# PR5004.net
KiCad netlist of a schematic drawn in EAGLE
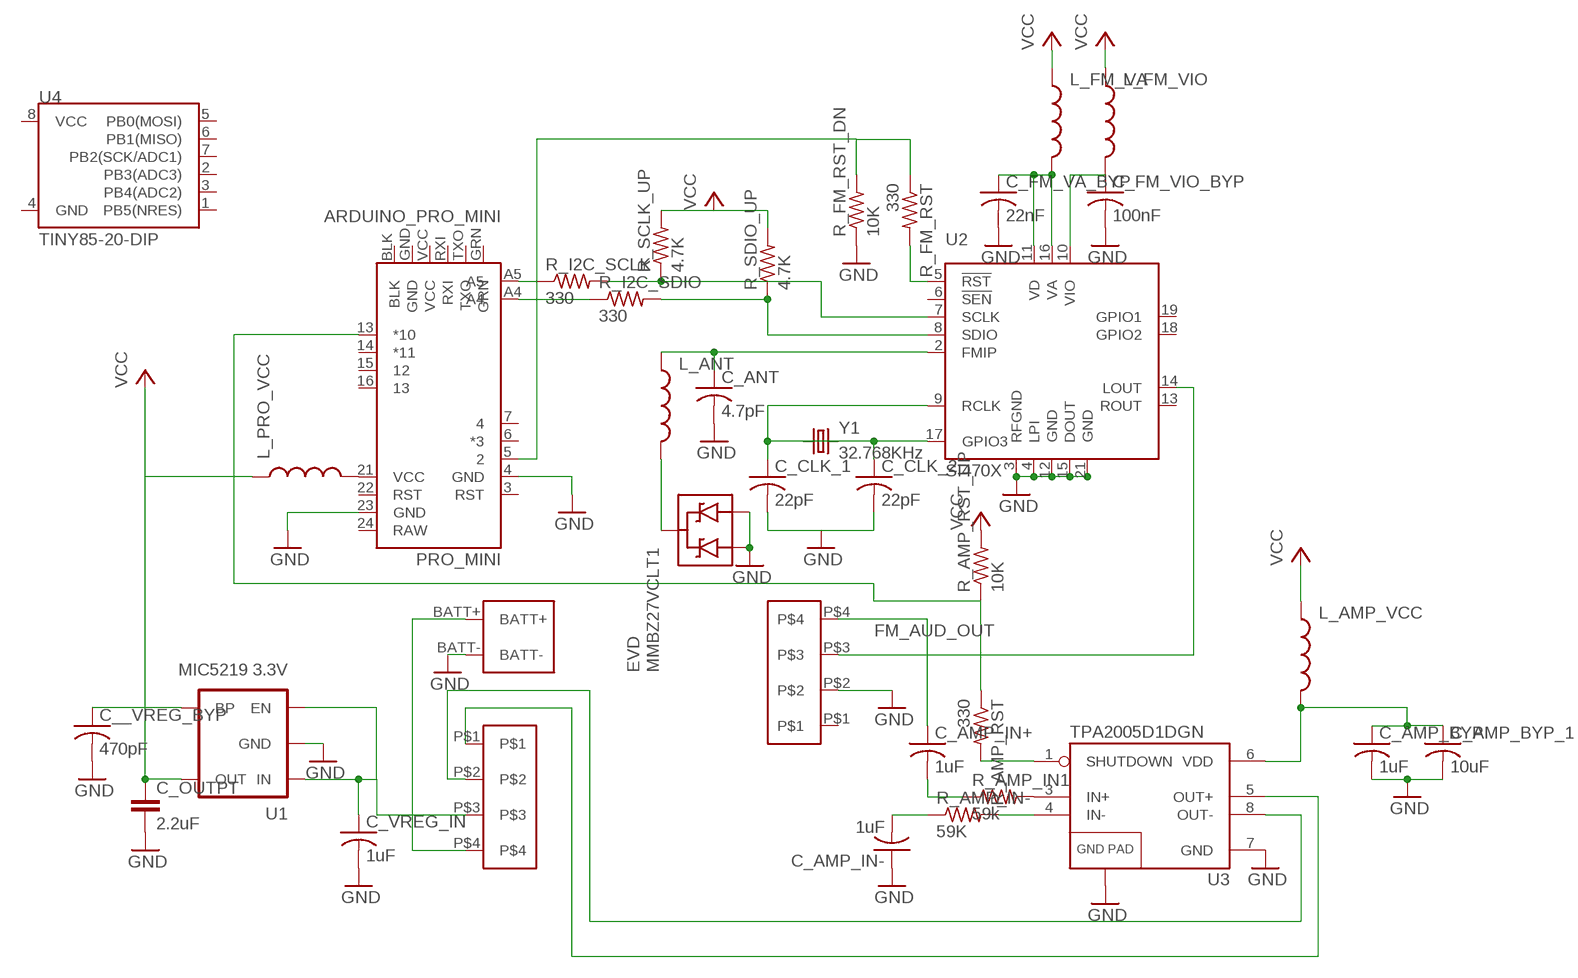
[diagram p0: schematic, sheet 1]

(export (version "E")
  (design (tool "Eeschema 10.0.6"))
  (components
    (comp (ref "ANT/POT_VOL")
      (value "OSTVN04")
      (footprint "eagle-import:OSTVN04")
      (libsource (lib "eagle-import") (part "OSTVN04"))
    )
    (comp (ref "ANT/POT_VOL1")
      (value "OSTVN04")
      (footprint "eagle-import:OSTVN04")
      (libsource (lib "eagle-import") (part "OSTVN04"))
    )
    (comp (ref "BATT_IN")
      (value "KEYSTONE_2479_3XAAA_BOTTOM")
      (footprint "eagle-import:KEYSTONE_2479_3XAAA_BOTTOM")
      (libsource (lib "eagle-import") (part "KEYSTONE_2479_3XAAA_BOTTOM"))
    )
    (comp (ref "C_AMP_BYP")
      (value "1uF")
      (footprint "eagle-import:C0603")
      (libsource (lib "eagle-import") (part "C-USC0603"))
    )
    (comp (ref "C_AMP_BYP_1")
      (value "10uF")
      (footprint "eagle-import:C0603")
      (libsource (lib "eagle-import") (part "C-USC0603"))
    )
    (comp (ref "C_AMP_IN+")
      (value "1uF")
      (footprint "eagle-import:C0603")
      (libsource (lib "eagle-import") (part "C-USC0603"))
    )
    (comp (ref "C_AMP_IN-")
      (value "1uF")
      (footprint "eagle-import:C0603")
      (libsource (lib "eagle-import") (part "C-USC0603"))
    )
    (comp (ref "C_ANT")
      (value "4.7pF")
      (footprint "eagle-import:C0805")
      (libsource (lib "eagle-import") (part "C-USC0805"))
    )
    (comp (ref "C_CLK_1")
      (value "22pF")
      (footprint "eagle-import:C0603")
      (libsource (lib "eagle-import") (part "C-USC0603"))
    )
    (comp (ref "C_CLK_2")
      (value "22pF")
      (footprint "eagle-import:C0603")
      (libsource (lib "eagle-import") (part "C-USC0603"))
    )
    (comp (ref "C_FM_VA_BYP")
      (value "22nF")
      (footprint "eagle-import:C0603")
      (libsource (lib "eagle-import") (part "C-USC0603"))
    )
    (comp (ref "C_FM_VIO_BYP")
      (value "100nF")
      (footprint "eagle-import:C0603")
      (libsource (lib "eagle-import") (part "C-USC0603"))
    )
    (comp (ref "C_OUTPT")
      (value "2.2uF")
      (footprint "eagle-import:VISHAY_TR3C")
      (libsource (lib "eagle-import") (part "VISHAY_TR3C"))
    )
    (comp (ref "C_VREG_IN")
      (value "1uF")
      (footprint "eagle-import:C0603")
      (libsource (lib "eagle-import") (part "C-USC0603"))
    )
    (comp (ref "C__VREG_BYP")
      (value "470pF")
      (footprint "eagle-import:C0603")
      (libsource (lib "eagle-import") (part "C-USC0603"))
    )
    (comp (ref "EVD")
      (value "MMBZ27VCLT1")
      (footprint "eagle-import:SOT23-3")
      (libsource (lib "eagle-import") (part "MMBZ27VCLT1"))
    )
    (comp (ref "L_AMP_VCC")
      (value "INDUCTOR0603")
      (footprint "eagle-import:0603")
      (libsource (lib "eagle-import") (part "INDUCTOR0603"))
    )
    (comp (ref "L_ANT")
      (value "INDUCTOR0805")
      (footprint "eagle-import:0805")
      (libsource (lib "eagle-import") (part "INDUCTOR0805"))
    )
    (comp (ref "L_FM_VA")
      (value "INDUCTOR0603")
      (footprint "eagle-import:0603")
      (libsource (lib "eagle-import") (part "INDUCTOR0603"))
    )
    (comp (ref "L_FM_VIO")
      (value "INDUCTOR0603")
      (footprint "eagle-import:0603")
      (libsource (lib "eagle-import") (part "INDUCTOR0603"))
    )
    (comp (ref "L_PRO_VCC")
      (value "INDUCTOR0603")
      (footprint "eagle-import:0603")
      (libsource (lib "eagle-import") (part "INDUCTOR0603"))
    )
    (comp (ref "PRO_MINI")
      (value "ARDUINO_PRO_MINI")
      (footprint "eagle-import:ARDUINO_PRO_MINI")
      (libsource (lib "eagle-import") (part "ARDUINO_PRO_MINI"))
    )
    (comp (ref "R_AMP_IN-")
      (value "59K")
      (footprint "eagle-import:R0603")
      (libsource (lib "eagle-import") (part "R-US_R0603"))
    )
    (comp (ref "R_AMP_IN1")
      (value "59k")
      (footprint "eagle-import:R0603")
      (libsource (lib "eagle-import") (part "R-US_R0603"))
    )
    (comp (ref "R_AMP_RST")
      (value "330")
      (footprint "eagle-import:R0603")
      (libsource (lib "eagle-import") (part "R-US_R0603"))
    )
    (comp (ref "R_AMP_RST_UP")
      (value "10K")
      (footprint "eagle-import:R0603")
      (libsource (lib "eagle-import") (part "R-US_R0603"))
    )
    (comp (ref "R_FM_RST")
      (value "330")
      (footprint "eagle-import:R0603")
      (libsource (lib "eagle-import") (part "R-US_R0603"))
    )
    (comp (ref "R_FM_RST_DN")
      (value "10K")
      (footprint "eagle-import:R0603")
      (libsource (lib "eagle-import") (part "R-US_R0603"))
    )
    (comp (ref "R_I2C_SCLK")
      (value "330")
      (footprint "eagle-import:R0603")
      (libsource (lib "eagle-import") (part "R-US_R0603"))
    )
    (comp (ref "R_I2C_SDIO")
      (value "330")
      (footprint "eagle-import:R0603")
      (libsource (lib "eagle-import") (part "R-US_R0603"))
    )
    (comp (ref "R_SCLK_UP")
      (value "4.7K")
      (footprint "eagle-import:R0603")
      (libsource (lib "eagle-import") (part "R-US_R0603"))
    )
    (comp (ref "R_SDIO_UP")
      (value "4.7K")
      (footprint "eagle-import:R0603")
      (libsource (lib "eagle-import") (part "R-US_R0603"))
    )
    (comp (ref "U1")
      (value "MIC5219 3.3V")
      (footprint "eagle-import:SOT23-5")
      (libsource (lib "eagle-import") (part "V_REG_MIC52193.3V"))
    )
    (comp (ref "U2")
      (value "SI470X")
      (footprint "eagle-import:SI470X")
      (libsource (lib "eagle-import") (part "SI470X"))
    )
    (comp (ref "U3")
      (value "TPA2005D1DGN")
      (footprint "eagle-import:POWER-SOP8")
      (libsource (lib "eagle-import") (part "TPA2005D1DGN"))
    )
    (comp (ref "U4")
      (value "TINY85-20-DIP")
      (footprint "eagle-import:DIP08")
      (libsource (lib "eagle-import") (part "ATTINY45TINY85-20-DIP"))
    )
    (comp (ref "Y1")
      (value "32.768KHz")
      (footprint "eagle-import:CRYSTAL-32KHZ-SMD")
      (libsource (lib "eagle-import") (part "CRYSTAL32-SMD"))
    )
  )
  (nets
    (net (code "1") (name "/FM_AUD_OUT") (class "Default")
      (node (ref "ANT/POT_VOL") (pin "P$3") (pinfunction "P$3_P$3") (pintype "bidirectional"))
      (node (ref "U2") (pin "14") (pinfunction "LOUT_14") (pintype "bidirectional"))
    )
    (net (code "2") (name "GND") (class "Default")
      (node (ref "ANT/POT_VOL") (pin "P$2") (pinfunction "P$2_P$2") (pintype "bidirectional"))
      (node (ref "BATT_IN") (pin "BATT-") (pinfunction "BATT-_BATT-") (pintype "bidirectional"))
      (node (ref "C_AMP_BYP") (pin "2") (pinfunction "2_2") (pintype "passive"))
      (node (ref "C_AMP_BYP_1") (pin "2") (pinfunction "2_2") (pintype "passive"))
      (node (ref "C_AMP_IN-") (pin "1") (pinfunction "1_1") (pintype "passive"))
      (node (ref "C_ANT") (pin "2") (pinfunction "2_2") (pintype "passive"))
      (node (ref "C_CLK_1") (pin "2") (pinfunction "2_2") (pintype "passive"))
      (node (ref "C_CLK_2") (pin "2") (pinfunction "2_2") (pintype "passive"))
      (node (ref "C_FM_VA_BYP") (pin "2") (pinfunction "2_2") (pintype "passive"))
      (node (ref "C_FM_VIO_BYP") (pin "2") (pinfunction "2_2") (pintype "passive"))
      (node (ref "C_OUTPT") (pin "P$2") (pinfunction "2_P$2") (pintype "passive"))
      (node (ref "C_VREG_IN") (pin "2") (pinfunction "2_2") (pintype "passive"))
      (node (ref "C__VREG_BYP") (pin "2") (pinfunction "2_2") (pintype "passive"))
      (node (ref "EVD") (pin "1") (pinfunction "A1_1") (pintype "passive"))
      (node (ref "EVD") (pin "2") (pinfunction "A2_2") (pintype "passive"))
      (node (ref "PRO_MINI") (pin "23") (pinfunction "GND_23") (pintype "bidirectional"))
      (node (ref "PRO_MINI") (pin "4") (pinfunction "GND_4") (pintype "bidirectional"))
      (node (ref "R_FM_RST_DN") (pin "1") (pinfunction "1_1") (pintype "passive"))
      (node (ref "U1") (pin "2") (pinfunction "GND_2") (pintype "input"))
      (node (ref "U2") (pin "12") (pinfunction "GND_12") (pintype "bidirectional"))
      (node (ref "U2") (pin "15") (pinfunction "DOUT_15") (pintype "bidirectional"))
      (node (ref "U2") (pin "21") (pinfunction "GND_21") (pintype "bidirectional"))
      (node (ref "U2") (pin "3") (pinfunction "RFGND_3") (pintype "bidirectional"))
      (node (ref "U2") (pin "4") (pinfunction "LPI_4") (pintype "bidirectional"))
      (node (ref "U3") (pin "7") (pinfunction "GND_7") (pintype "power_in"))
      (node (ref "U3") (pin "9") (pinfunction "GND_9") (pintype "power_in"))
    )
    (net (code "3") (name "Net-(ANT/POT_VOL-PadP$4)") (class "Default")
      (node (ref "ANT/POT_VOL") (pin "P$4") (pinfunction "P$4_P$4") (pintype "bidirectional"))
      (node (ref "C_AMP_IN+") (pin "1") (pinfunction "1_1") (pintype "passive"))
    )
    (net (code "4") (name "Net-(ANT/POT_VOL1-PadP$4)") (class "Default")
      (node (ref "ANT/POT_VOL1") (pin "P$4") (pinfunction "P$4_P$4") (pintype "bidirectional"))
      (node (ref "BATT_IN") (pin "BATT+") (pinfunction "BATT+_BATT+") (pintype "bidirectional"))
    )
    (net (code "5") (name "Net-(C_AMP_IN+-Pad2)") (class "Default")
      (node (ref "C_AMP_IN+") (pin "2") (pinfunction "2_2") (pintype "passive"))
      (node (ref "R_AMP_IN1") (pin "1") (pinfunction "1_1") (pintype "passive"))
    )
    (net (code "6") (name "Net-(C_AMP_IN--Pad2)") (class "Default")
      (node (ref "C_AMP_IN-") (pin "2") (pinfunction "2_2") (pintype "passive"))
      (node (ref "R_AMP_IN-") (pin "1") (pinfunction "1_1") (pintype "passive"))
    )
    (net (code "7") (name "Net-(EVD-C)") (class "Default")
      (node (ref "EVD") (pin "3") (pinfunction "C_3") (pintype "passive"))
      (node (ref "L_ANT") (pin "2") (pinfunction "2_2") (pintype "passive"))
    )
    (net (code "8") (name "Net-(L_PRO_VCC-Pad2)") (class "Default")
      (node (ref "L_PRO_VCC") (pin "2") (pinfunction "2_2") (pintype "passive"))
      (node (ref "PRO_MINI") (pin "21") (pinfunction "VCC_21") (pintype "bidirectional"))
    )
    (net (code "9") (name "Net-(PRO_MINI-*10)") (class "Default")
      (node (ref "PRO_MINI") (pin "13") (pinfunction "*10_13") (pintype "bidirectional"))
      (node (ref "R_AMP_RST") (pin "1") (pinfunction "1_1") (pintype "passive"))
      (node (ref "R_AMP_RST_UP") (pin "1") (pinfunction "1_1") (pintype "passive"))
    )
    (net (code "10") (name "Net-(PRO_MINI-2)") (class "Default")
      (node (ref "PRO_MINI") (pin "5") (pinfunction "2_5") (pintype "bidirectional"))
      (node (ref "R_FM_RST") (pin "1") (pinfunction "1_1") (pintype "passive"))
      (node (ref "R_FM_RST_DN") (pin "2") (pinfunction "2_2") (pintype "passive"))
    )
    (net (code "11") (name "Net-(PRO_MINI-PadA4)") (class "Default")
      (node (ref "PRO_MINI") (pin "A4") (pinfunction "A4_A4") (pintype "bidirectional"))
      (node (ref "R_I2C_SDIO") (pin "1") (pinfunction "1_1") (pintype "passive"))
    )
    (net (code "12") (name "Net-(PRO_MINI-PadA5)") (class "Default")
      (node (ref "PRO_MINI") (pin "A5") (pinfunction "A5_A5") (pintype "bidirectional"))
      (node (ref "R_I2C_SCLK") (pin "1") (pinfunction "1_1") (pintype "passive"))
    )
    (net (code "13") (name "Net-(U1-BP)") (class "Default")
      (node (ref "C__VREG_BYP") (pin "1") (pinfunction "1_1") (pintype "passive"))
      (node (ref "U1") (pin "4") (pinfunction "BP_4") (pintype "input"))
    )
    (net (code "14") (name "Net-(U1-EN)") (class "Default")
      (node (ref "ANT/POT_VOL1") (pin "P$3") (pinfunction "P$3_P$3") (pintype "bidirectional"))
      (node (ref "C_VREG_IN") (pin "1") (pinfunction "1_1") (pintype "passive"))
      (node (ref "U1") (pin "1") (pinfunction "IN_1") (pintype "input"))
      (node (ref "U1") (pin "3") (pinfunction "EN_3") (pintype "input"))
    )
    (net (code "15") (name "Net-(U2-FMIP)") (class "Default")
      (node (ref "C_ANT") (pin "1") (pinfunction "1_1") (pintype "passive"))
      (node (ref "L_ANT") (pin "1") (pinfunction "1_1") (pintype "passive"))
      (node (ref "U2") (pin "2") (pinfunction "FMIP_2") (pintype "bidirectional"))
    )
    (net (code "16") (name "Net-(U2-GPIO3)") (class "Default")
      (node (ref "C_CLK_2") (pin "1") (pinfunction "1_1") (pintype "passive"))
      (node (ref "U2") (pin "17") (pinfunction "GPIO3_17") (pintype "bidirectional"))
      (node (ref "Y1") (pin "X1") (pinfunction "1_X1") (pintype "passive"))
    )
    (net (code "17") (name "Net-(U2-RCLK)") (class "Default")
      (node (ref "C_CLK_1") (pin "1") (pinfunction "1_1") (pintype "passive"))
      (node (ref "U2") (pin "9") (pinfunction "RCLK_9") (pintype "bidirectional"))
      (node (ref "Y1") (pin "X2") (pinfunction "2_X2") (pintype "passive"))
    )
    (net (code "18") (name "Net-(U2-SCLK)") (class "Default")
      (node (ref "R_I2C_SCLK") (pin "2") (pinfunction "2_2") (pintype "passive"))
      (node (ref "R_SCLK_UP") (pin "1") (pinfunction "1_1") (pintype "passive"))
      (node (ref "U2") (pin "7") (pinfunction "SCLK_7") (pintype "bidirectional"))
    )
    (net (code "19") (name "Net-(U2-SDIO)") (class "Default")
      (node (ref "R_I2C_SDIO") (pin "2") (pinfunction "2_2") (pintype "passive"))
      (node (ref "R_SDIO_UP") (pin "1") (pinfunction "1_1") (pintype "passive"))
      (node (ref "U2") (pin "8") (pinfunction "SDIO_8") (pintype "bidirectional"))
    )
    (net (code "20") (name "Net-(U2-VA)") (class "Default")
      (node (ref "C_FM_VA_BYP") (pin "1") (pinfunction "1_1") (pintype "passive"))
      (node (ref "L_FM_VA") (pin "2") (pinfunction "2_2") (pintype "passive"))
      (node (ref "U2") (pin "11") (pinfunction "VD_11") (pintype "bidirectional"))
      (node (ref "U2") (pin "16") (pinfunction "VA_16") (pintype "bidirectional"))
    )
    (net (code "21") (name "Net-(U2-VIO)") (class "Default")
      (node (ref "C_FM_VIO_BYP") (pin "1") (pinfunction "1_1") (pintype "passive"))
      (node (ref "L_FM_VIO") (pin "2") (pinfunction "2_2") (pintype "passive"))
      (node (ref "U2") (pin "10") (pinfunction "VIO_10") (pintype "bidirectional"))
    )
    (net (code "22") (name "Net-(U2-~{RST})") (class "Default")
      (node (ref "R_FM_RST") (pin "2") (pinfunction "2_2") (pintype "passive"))
      (node (ref "U2") (pin "5") (pinfunction "~{RST}_5") (pintype "bidirectional"))
    )
    (net (code "23") (name "Net-(U3-IN+)") (class "Default")
      (node (ref "R_AMP_IN1") (pin "2") (pinfunction "2_2") (pintype "passive"))
      (node (ref "U3") (pin "3") (pinfunction "IN+_3") (pintype "bidirectional"))
    )
    (net (code "24") (name "Net-(U3-IN-)") (class "Default")
      (node (ref "R_AMP_IN-") (pin "2") (pinfunction "2_2") (pintype "passive"))
      (node (ref "U3") (pin "4") (pinfunction "IN-_4") (pintype "bidirectional"))
    )
    (net (code "25") (name "Net-(U3-OUT+)") (class "Default")
      (node (ref "ANT/POT_VOL1") (pin "P$1") (pinfunction "P$1_P$1") (pintype "bidirectional"))
      (node (ref "U3") (pin "5") (pinfunction "OUT+_5") (pintype "bidirectional"))
    )
    (net (code "26") (name "Net-(U3-OUT-)") (class "Default")
      (node (ref "ANT/POT_VOL1") (pin "P$2") (pinfunction "P$2_P$2") (pintype "bidirectional"))
      (node (ref "U3") (pin "8") (pinfunction "OUT-_8") (pintype "bidirectional"))
    )
    (net (code "27") (name "Net-(U3-SHUTDOWN)") (class "Default")
      (node (ref "R_AMP_RST") (pin "2") (pinfunction "2_2") (pintype "passive"))
      (node (ref "U3") (pin "1") (pinfunction "SHUTDOWN_1") (pintype "input"))
    )
    (net (code "28") (name "Net-(U3-VDD)") (class "Default")
      (node (ref "C_AMP_BYP") (pin "1") (pinfunction "1_1") (pintype "passive"))
      (node (ref "C_AMP_BYP_1") (pin "1") (pinfunction "1_1") (pintype "passive"))
      (node (ref "L_AMP_VCC") (pin "2") (pinfunction "2_2") (pintype "passive"))
      (node (ref "U3") (pin "6") (pinfunction "VDD_6") (pintype "power_in"))
    )
    (net (code "29") (name "VCC") (class "Default")
      (node (ref "C_OUTPT") (pin "P$1") (pinfunction "1_P$1") (pintype "passive"))
      (node (ref "L_AMP_VCC") (pin "1") (pinfunction "1_1") (pintype "passive"))
      (node (ref "L_FM_VA") (pin "1") (pinfunction "1_1") (pintype "passive"))
      (node (ref "L_FM_VIO") (pin "1") (pinfunction "1_1") (pintype "passive"))
      (node (ref "L_PRO_VCC") (pin "1") (pinfunction "1_1") (pintype "passive"))
      (node (ref "R_AMP_RST_UP") (pin "2") (pinfunction "2_2") (pintype "passive"))
      (node (ref "R_SCLK_UP") (pin "2") (pinfunction "2_2") (pintype "passive"))
      (node (ref "R_SDIO_UP") (pin "2") (pinfunction "2_2") (pintype "passive"))
      (node (ref "U1") (pin "5") (pinfunction "OUT_5") (pintype "passive"))
    )
    (net (code "30") (name "unconnected-(ANT/POT_VOL-PadP$1)") (class "Default")
      (node (ref "ANT/POT_VOL") (pin "P$1") (pinfunction "P$1_P$1") (pintype "bidirectional"))
    )
    (net (code "31") (name "unconnected-(PRO_MINI-*3-Pad6)") (class "Default")
      (node (ref "PRO_MINI") (pin "6") (pinfunction "*3_6") (pintype "bidirectional"))
    )
    (net (code "32") (name "unconnected-(PRO_MINI-*11-Pad14)") (class "Default")
      (node (ref "PRO_MINI") (pin "14") (pinfunction "*11_14") (pintype "bidirectional"))
    )
    (net (code "33") (name "unconnected-(PRO_MINI-4-Pad7)") (class "Default")
      (node (ref "PRO_MINI") (pin "7") (pinfunction "4_7") (pintype "bidirectional"))
    )
    (net (code "34") (name "unconnected-(PRO_MINI-12-Pad15)") (class "Default")
      (node (ref "PRO_MINI") (pin "15") (pinfunction "12_15") (pintype "bidirectional"))
    )
    (net (code "35") (name "unconnected-(PRO_MINI-13-Pad16)") (class "Default")
      (node (ref "PRO_MINI") (pin "16") (pinfunction "13_16") (pintype "bidirectional"))
    )
    (net (code "36") (name "unconnected-(PRO_MINI-PadBLK)") (class "Default")
      (node (ref "PRO_MINI") (pin "BLK") (pinfunction "BLK_BLK") (pintype "bidirectional"))
    )
    (net (code "37") (name "unconnected-(PRO_MINI-PadGND)") (class "Default")
      (node (ref "PRO_MINI") (pin "GND") (pinfunction "GND_GND") (pintype "bidirectional"))
    )
    (net (code "38") (name "unconnected-(PRO_MINI-PadGRN)") (class "Default")
      (node (ref "PRO_MINI") (pin "GRN") (pinfunction "GRN_GRN") (pintype "bidirectional"))
    )
    (net (code "39") (name "unconnected-(PRO_MINI-PadRXI)") (class "Default")
      (node (ref "PRO_MINI") (pin "RXI") (pinfunction "RXI_RXI") (pintype "bidirectional"))
    )
    (net (code "40") (name "unconnected-(PRO_MINI-PadTXO)") (class "Default")
      (node (ref "PRO_MINI") (pin "TXO") (pinfunction "TXO_TXO") (pintype "bidirectional"))
    )
    (net (code "41") (name "unconnected-(PRO_MINI-PadVCC)") (class "Default")
      (node (ref "PRO_MINI") (pin "VCC") (pinfunction "VCC_VCC") (pintype "bidirectional"))
    )
    (net (code "42") (name "unconnected-(PRO_MINI-RAW-Pad24)") (class "Default")
      (node (ref "PRO_MINI") (pin "24") (pinfunction "RAW_24") (pintype "bidirectional"))
    )
    (net (code "43") (name "unconnected-(PRO_MINI-RST-Pad3)") (class "Default")
      (node (ref "PRO_MINI") (pin "3") (pinfunction "RST_3") (pintype "bidirectional"))
    )
    (net (code "44") (name "unconnected-(PRO_MINI-RST-Pad22)") (class "Default")
      (node (ref "PRO_MINI") (pin "22") (pinfunction "RST_22") (pintype "bidirectional"))
    )
    (net (code "45") (name "unconnected-(U2-GPIO1-Pad19)") (class "Default")
      (node (ref "U2") (pin "19") (pinfunction "GPIO1_19") (pintype "bidirectional"))
    )
    (net (code "46") (name "unconnected-(U2-GPIO2-Pad18)") (class "Default")
      (node (ref "U2") (pin "18") (pinfunction "GPIO2_18") (pintype "bidirectional"))
    )
    (net (code "47") (name "unconnected-(U2-ROUT-Pad13)") (class "Default")
      (node (ref "U2") (pin "13") (pinfunction "ROUT_13") (pintype "bidirectional"))
    )
    (net (code "48") (name "unconnected-(U2-~{SEN}-Pad6)") (class "Default")
      (node (ref "U2") (pin "6") (pinfunction "~{SEN}_6") (pintype "bidirectional"))
    )
    (net (code "49") (name "unconnected-(U4-GND-Pad4)") (class "Default")
      (node (ref "U4") (pin "4") (pinfunction "GND_4") (pintype "bidirectional"))
    )
    (net (code "50") (name "unconnected-(U4-PB0(MOSI)-Pad5)") (class "Default")
      (node (ref "U4") (pin "5") (pinfunction "PB0(MOSI)_5") (pintype "bidirectional"))
    )
    (net (code "51") (name "unconnected-(U4-PB1(MISO)-Pad6)") (class "Default")
      (node (ref "U4") (pin "6") (pinfunction "PB1(MISO)_6") (pintype "bidirectional"))
    )
    (net (code "52") (name "unconnected-(U4-PB2(SCK{slash}ADC1)-Pad7)") (class "Default")
      (node (ref "U4") (pin "7") (pinfunction "PB2(SCK/ADC1)_7") (pintype "bidirectional"))
    )
    (net (code "53") (name "unconnected-(U4-PB3(ADC3)-Pad2)") (class "Default")
      (node (ref "U4") (pin "2") (pinfunction "PB3(ADC3)_2") (pintype "bidirectional"))
    )
    (net (code "54") (name "unconnected-(U4-PB4(ADC2)-Pad3)") (class "Default")
      (node (ref "U4") (pin "3") (pinfunction "PB4(ADC2)_3") (pintype "bidirectional"))
    )
    (net (code "55") (name "unconnected-(U4-PB5(NRES)-Pad1)") (class "Default")
      (node (ref "U4") (pin "1") (pinfunction "PB5(NRES)_1") (pintype "bidirectional"))
    )
    (net (code "56") (name "unconnected-(U4-VCC-Pad8)") (class "Default")
      (node (ref "U4") (pin "8") (pinfunction "VCC_8") (pintype "bidirectional"))
    )
  )
)
